# snes_visualization_left.net
KiCad netlist of a schematic drawn in EAGLE
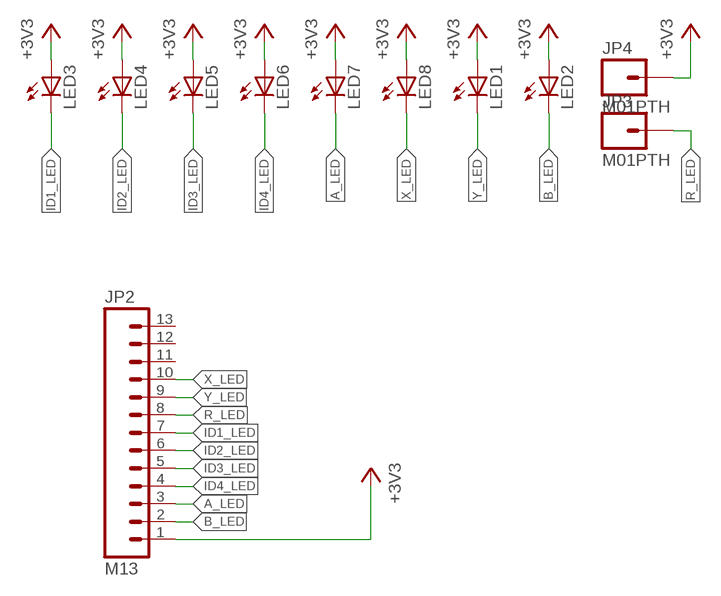
[diagram p0: schematic, sheet 1]

(export (version "E")
  (design (tool "Eeschema 10.0.6"))
  (components
    (comp (ref "JP2")
      (value "M13")
      (footprint "eagle-import:1X13")
      (libsource (lib "eagle-import") (part "M13"))
    )
    (comp (ref "JP3")
      (value "M01PTH")
      (footprint "eagle-import:1X01")
      (libsource (lib "eagle-import") (part "M01PTH"))
    )
    (comp (ref "JP4")
      (value "M01PTH")
      (footprint "eagle-import:1X01")
      (libsource (lib "eagle-import") (part "M01PTH"))
    )
    (comp (ref "LED1")
      (value "LED5MM")
      (footprint "eagle-import:LED5MM")
      (libsource (lib "eagle-import") (part "LED5MM"))
    )
    (comp (ref "LED2")
      (value "LED5MM")
      (footprint "eagle-import:LED5MM")
      (libsource (lib "eagle-import") (part "LED5MM"))
    )
    (comp (ref "LED3")
      (value "LED5MM")
      (footprint "eagle-import:LED5MM")
      (libsource (lib "eagle-import") (part "LED5MM"))
    )
    (comp (ref "LED4")
      (value "LED5MM")
      (footprint "eagle-import:LED5MM")
      (libsource (lib "eagle-import") (part "LED5MM"))
    )
    (comp (ref "LED5")
      (value "LED5MM")
      (footprint "eagle-import:LED5MM")
      (libsource (lib "eagle-import") (part "LED5MM"))
    )
    (comp (ref "LED6")
      (value "LED5MM")
      (footprint "eagle-import:LED5MM")
      (libsource (lib "eagle-import") (part "LED5MM"))
    )
    (comp (ref "LED7")
      (value "LED5MM")
      (footprint "eagle-import:LED5MM")
      (libsource (lib "eagle-import") (part "LED5MM"))
    )
    (comp (ref "LED8")
      (value "LED5MM")
      (footprint "eagle-import:LED5MM")
      (libsource (lib "eagle-import") (part "LED5MM"))
    )
  )
  (nets
    (net (code "1") (name "+3V3") (class "Default")
      (node (ref "JP2") (pin "1") (pinfunction "1_1") (pintype "passive"))
      (node (ref "JP4") (pin "1") (pinfunction "1_1") (pintype "passive"))
      (node (ref "LED1") (pin "A") (pinfunction "A_A") (pintype "passive"))
      (node (ref "LED2") (pin "A") (pinfunction "A_A") (pintype "passive"))
      (node (ref "LED3") (pin "A") (pinfunction "A_A") (pintype "passive"))
      (node (ref "LED4") (pin "A") (pinfunction "A_A") (pintype "passive"))
      (node (ref "LED5") (pin "A") (pinfunction "A_A") (pintype "passive"))
      (node (ref "LED6") (pin "A") (pinfunction "A_A") (pintype "passive"))
      (node (ref "LED7") (pin "A") (pinfunction "A_A") (pintype "passive"))
      (node (ref "LED8") (pin "A") (pinfunction "A_A") (pintype "passive"))
    )
    (net (code "2") (name "A_LED") (class "Default")
      (node (ref "JP2") (pin "3") (pinfunction "3_3") (pintype "passive"))
      (node (ref "LED7") (pin "K") (pinfunction "C_K") (pintype "passive"))
    )
    (net (code "3") (name "B_LED") (class "Default")
      (node (ref "JP2") (pin "2") (pinfunction "2_2") (pintype "passive"))
      (node (ref "LED2") (pin "K") (pinfunction "C_K") (pintype "passive"))
    )
    (net (code "4") (name "ID1_LED") (class "Default")
      (node (ref "JP2") (pin "7") (pinfunction "7_7") (pintype "passive"))
      (node (ref "LED3") (pin "K") (pinfunction "C_K") (pintype "passive"))
    )
    (net (code "5") (name "ID2_LED") (class "Default")
      (node (ref "JP2") (pin "6") (pinfunction "6_6") (pintype "passive"))
      (node (ref "LED4") (pin "K") (pinfunction "C_K") (pintype "passive"))
    )
    (net (code "6") (name "ID3_LED") (class "Default")
      (node (ref "JP2") (pin "5") (pinfunction "5_5") (pintype "passive"))
      (node (ref "LED5") (pin "K") (pinfunction "C_K") (pintype "passive"))
    )
    (net (code "7") (name "ID4_LED") (class "Default")
      (node (ref "JP2") (pin "4") (pinfunction "4_4") (pintype "passive"))
      (node (ref "LED6") (pin "K") (pinfunction "C_K") (pintype "passive"))
    )
    (net (code "8") (name "R_LED") (class "Default")
      (node (ref "JP2") (pin "8") (pinfunction "8_8") (pintype "passive"))
      (node (ref "JP3") (pin "1") (pinfunction "1_1") (pintype "passive"))
    )
    (net (code "9") (name "X_LED") (class "Default")
      (node (ref "JP2") (pin "10") (pinfunction "10_10") (pintype "passive"))
      (node (ref "LED8") (pin "K") (pinfunction "C_K") (pintype "passive"))
    )
    (net (code "10") (name "Y_LED") (class "Default")
      (node (ref "JP2") (pin "9") (pinfunction "9_9") (pintype "passive"))
      (node (ref "LED1") (pin "K") (pinfunction "C_K") (pintype "passive"))
    )
    (net (code "11") (name "unconnected-(JP2-Pad11)") (class "Default")
      (node (ref "JP2") (pin "11") (pinfunction "11_11") (pintype "passive"))
    )
    (net (code "12") (name "unconnected-(JP2-Pad12)") (class "Default")
      (node (ref "JP2") (pin "12") (pinfunction "12_12") (pintype "passive"))
    )
    (net (code "13") (name "unconnected-(JP2-Pad13)") (class "Default")
      (node (ref "JP2") (pin "13") (pinfunction "13_13") (pintype "passive"))
    )
  )
)
